# Gates.net
KiCad netlist of a schematic drawn in Altium Designer
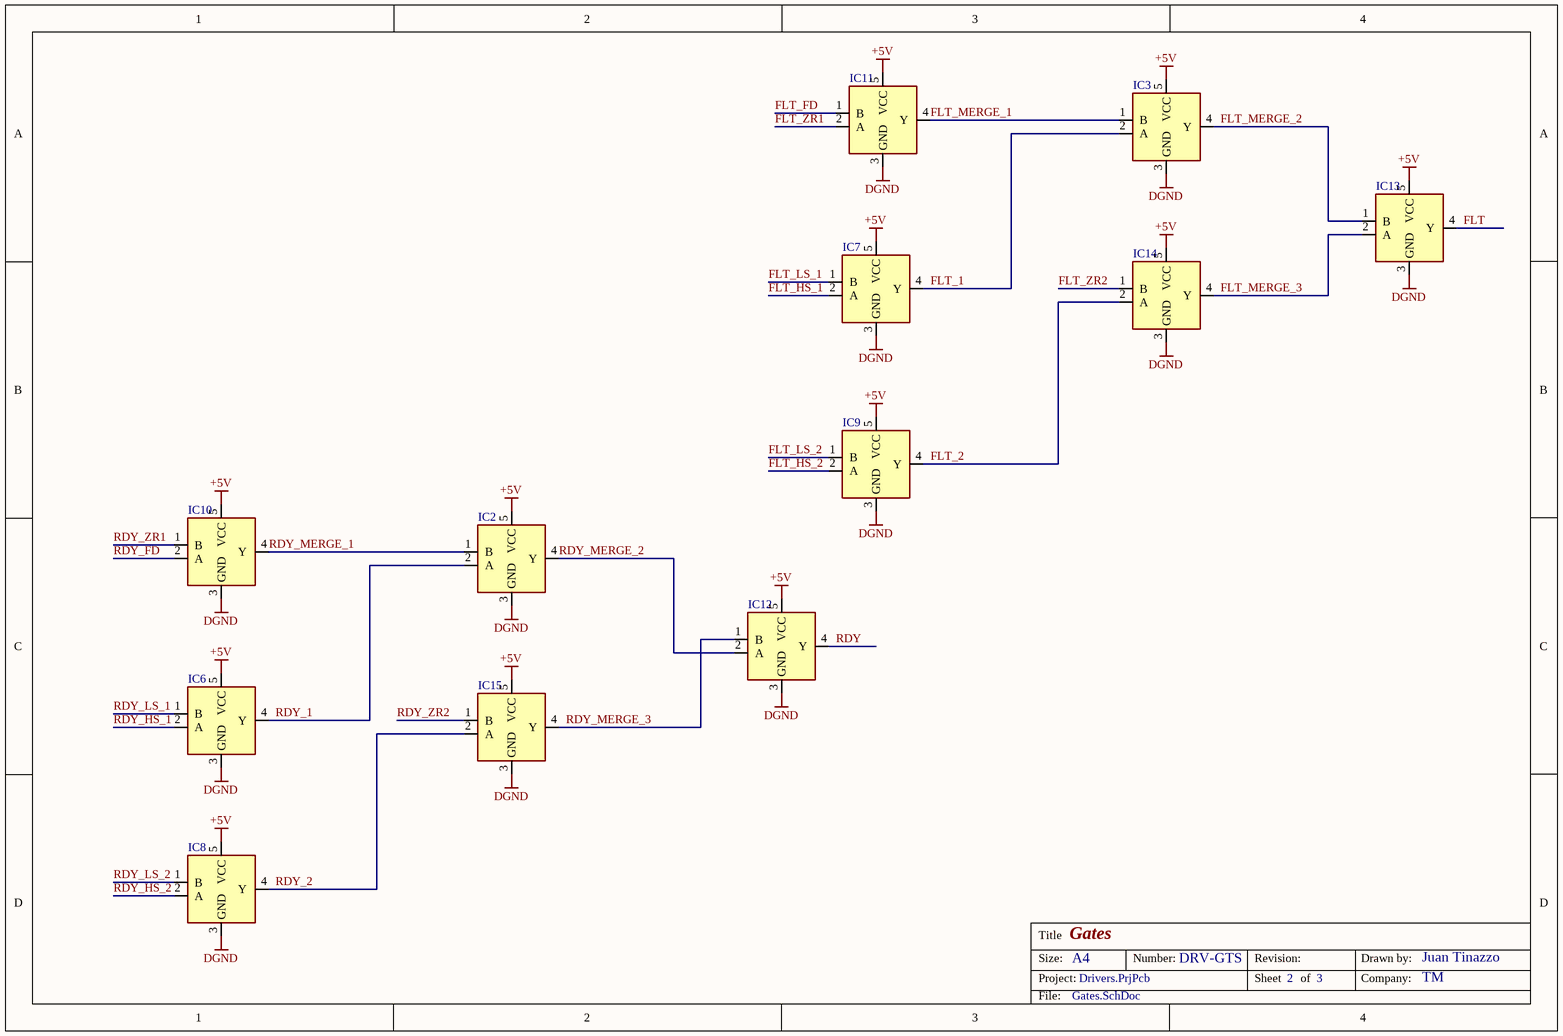
[diagram p0: Gates.SchDoc]

(export (version "E")
  (design (tool "Eeschema 10.0.6"))
  (components
    (comp (ref "IC2")
      (value "74LVC1G08GW,125")
      (footprint "SamacSys:SOT65P210X110-5N")
      (description "Integrated Circuit")
      (fields (field (name "MOUSER PART NUMBER") "771-74LVC1G08GW-G"))
      (libsource (lib "SamacSys") (part "74LVC1G08GW,125"))
    )
    (comp (ref "IC3")
      (value "74LVC1G08GW,125")
      (footprint "SamacSys:SOT65P210X110-5N")
      (description "Integrated Circuit")
      (fields (field (name "MOUSER PART NUMBER") "771-74LVC1G08GW-G"))
      (libsource (lib "SamacSys") (part "74LVC1G08GW,125"))
    )
    (comp (ref "IC6")
      (value "74LVC1G08GW,125")
      (footprint "SamacSys:SOT65P210X110-5N")
      (description "Integrated Circuit")
      (fields (field (name "MOUSER PART NUMBER") "771-74LVC1G08GW-G"))
      (libsource (lib "SamacSys") (part "74LVC1G08GW,125"))
    )
    (comp (ref "IC7")
      (value "74LVC1G08GW,125")
      (footprint "SamacSys:SOT65P210X110-5N")
      (description "Integrated Circuit")
      (fields (field (name "MOUSER PART NUMBER") "771-74LVC1G08GW-G"))
      (libsource (lib "SamacSys") (part "74LVC1G08GW,125"))
    )
    (comp (ref "IC8")
      (value "74LVC1G08GW,125")
      (footprint "SamacSys:SOT65P210X110-5N")
      (description "Integrated Circuit")
      (fields (field (name "MOUSER PART NUMBER") "771-74LVC1G08GW-G"))
      (libsource (lib "SamacSys") (part "74LVC1G08GW,125"))
    )
    (comp (ref "IC9")
      (value "74LVC1G08GW,125")
      (footprint "SamacSys:SOT65P210X110-5N")
      (description "Integrated Circuit")
      (fields (field (name "MOUSER PART NUMBER") "771-74LVC1G08GW-G"))
      (libsource (lib "SamacSys") (part "74LVC1G08GW,125"))
    )
    (comp (ref "IC10")
      (value "74LVC1G08GW,125")
      (footprint "SamacSys:SOT65P210X110-5N")
      (description "Integrated Circuit")
      (fields (field (name "MOUSER PART NUMBER") "771-74LVC1G08GW-G"))
      (libsource (lib "SamacSys") (part "74LVC1G08GW,125"))
    )
    (comp (ref "IC11")
      (value "74LVC1G08GW,125")
      (footprint "SamacSys:SOT65P210X110-5N")
      (description "Integrated Circuit")
      (fields (field (name "MOUSER PART NUMBER") "771-74LVC1G08GW-G"))
      (libsource (lib "SamacSys") (part "74LVC1G08GW,125"))
    )
    (comp (ref "IC12")
      (value "74LVC1G08GW,125")
      (footprint "SamacSys:SOT65P210X110-5N")
      (description "Integrated Circuit")
      (fields (field (name "MOUSER PART NUMBER") "771-74LVC1G08GW-G"))
      (libsource (lib "SamacSys") (part "74LVC1G08GW,125"))
    )
    (comp (ref "IC13")
      (value "74LVC1G08GW,125")
      (footprint "SamacSys:SOT65P210X110-5N")
      (description "Integrated Circuit")
      (fields (field (name "MOUSER PART NUMBER") "771-74LVC1G08GW-G"))
      (libsource (lib "SamacSys") (part "74LVC1G08GW,125"))
    )
    (comp (ref "IC14")
      (value "74LVC1G08GW,125")
      (footprint "SamacSys:SOT65P210X110-5N")
      (description "Integrated Circuit")
      (fields (field (name "MOUSER PART NUMBER") "771-74LVC1G08GW-G"))
      (libsource (lib "SamacSys") (part "74LVC1G08GW,125"))
    )
    (comp (ref "IC15")
      (value "74LVC1G08GW,125")
      (footprint "SamacSys:SOT65P210X110-5N")
      (description "Integrated Circuit")
      (fields (field (name "MOUSER PART NUMBER") "771-74LVC1G08GW-G"))
      (libsource (lib "SamacSys") (part "74LVC1G08GW,125"))
    )
  )
  (nets
    (net (code "1") (name "+5V") (class "Default")
      (node (ref "IC10") (pin "5") (pinfunction "VCC_5") (pintype "passive"))
      (node (ref "IC11") (pin "5") (pinfunction "VCC_5") (pintype "passive"))
      (node (ref "IC12") (pin "5") (pinfunction "VCC_5") (pintype "passive"))
      (node (ref "IC13") (pin "5") (pinfunction "VCC_5") (pintype "passive"))
      (node (ref "IC14") (pin "5") (pinfunction "VCC_5") (pintype "passive"))
      (node (ref "IC15") (pin "5") (pinfunction "VCC_5") (pintype "passive"))
      (node (ref "IC2") (pin "5") (pinfunction "VCC_5") (pintype "passive"))
      (node (ref "IC3") (pin "5") (pinfunction "VCC_5") (pintype "passive"))
      (node (ref "IC6") (pin "5") (pinfunction "VCC_5") (pintype "passive"))
      (node (ref "IC7") (pin "5") (pinfunction "VCC_5") (pintype "passive"))
      (node (ref "IC8") (pin "5") (pinfunction "VCC_5") (pintype "passive"))
      (node (ref "IC9") (pin "5") (pinfunction "VCC_5") (pintype "passive"))
    )
    (net (code "2") (name "/FLT") (class "Default")
      (node (ref "IC13") (pin "4") (pinfunction "Y_4") (pintype "passive"))
    )
    (net (code "3") (name "/FLT_1") (class "Default")
      (node (ref "IC3") (pin "2") (pinfunction "A_2") (pintype "passive"))
      (node (ref "IC7") (pin "4") (pinfunction "Y_4") (pintype "passive"))
    )
    (net (code "4") (name "/FLT_2") (class "Default")
      (node (ref "IC14") (pin "2") (pinfunction "A_2") (pintype "passive"))
      (node (ref "IC9") (pin "4") (pinfunction "Y_4") (pintype "passive"))
    )
    (net (code "5") (name "/FLT_FD") (class "Default")
      (node (ref "IC11") (pin "1") (pinfunction "B_1") (pintype "passive"))
    )
    (net (code "6") (name "/FLT_HS_1") (class "Default")
      (node (ref "IC7") (pin "2") (pinfunction "A_2") (pintype "passive"))
    )
    (net (code "7") (name "/FLT_HS_2") (class "Default")
      (node (ref "IC9") (pin "2") (pinfunction "A_2") (pintype "passive"))
    )
    (net (code "8") (name "/FLT_LS_1") (class "Default")
      (node (ref "IC7") (pin "1") (pinfunction "B_1") (pintype "passive"))
    )
    (net (code "9") (name "/FLT_LS_2") (class "Default")
      (node (ref "IC9") (pin "1") (pinfunction "B_1") (pintype "passive"))
    )
    (net (code "10") (name "/FLT_MERGE_1") (class "Default")
      (node (ref "IC11") (pin "4") (pinfunction "Y_4") (pintype "passive"))
      (node (ref "IC3") (pin "1") (pinfunction "B_1") (pintype "passive"))
    )
    (net (code "11") (name "/FLT_MERGE_2") (class "Default")
      (node (ref "IC13") (pin "1") (pinfunction "B_1") (pintype "passive"))
      (node (ref "IC3") (pin "4") (pinfunction "Y_4") (pintype "passive"))
    )
    (net (code "12") (name "/FLT_MERGE_3") (class "Default")
      (node (ref "IC13") (pin "2") (pinfunction "A_2") (pintype "passive"))
      (node (ref "IC14") (pin "4") (pinfunction "Y_4") (pintype "passive"))
    )
    (net (code "13") (name "/FLT_ZR1") (class "Default")
      (node (ref "IC11") (pin "2") (pinfunction "A_2") (pintype "passive"))
    )
    (net (code "14") (name "/FLT_ZR2") (class "Default")
      (node (ref "IC14") (pin "1") (pinfunction "B_1") (pintype "passive"))
    )
    (net (code "15") (name "/RDY") (class "Default")
      (node (ref "IC12") (pin "4") (pinfunction "Y_4") (pintype "passive"))
    )
    (net (code "16") (name "/RDY_1") (class "Default")
      (node (ref "IC2") (pin "2") (pinfunction "A_2") (pintype "passive"))
      (node (ref "IC6") (pin "4") (pinfunction "Y_4") (pintype "passive"))
    )
    (net (code "17") (name "/RDY_2") (class "Default")
      (node (ref "IC15") (pin "2") (pinfunction "A_2") (pintype "passive"))
      (node (ref "IC8") (pin "4") (pinfunction "Y_4") (pintype "passive"))
    )
    (net (code "18") (name "/RDY_FD") (class "Default")
      (node (ref "IC10") (pin "2") (pinfunction "A_2") (pintype "passive"))
    )
    (net (code "19") (name "/RDY_HS_1") (class "Default")
      (node (ref "IC6") (pin "2") (pinfunction "A_2") (pintype "passive"))
    )
    (net (code "20") (name "/RDY_HS_2") (class "Default")
      (node (ref "IC8") (pin "2") (pinfunction "A_2") (pintype "passive"))
    )
    (net (code "21") (name "/RDY_LS_1") (class "Default")
      (node (ref "IC6") (pin "1") (pinfunction "B_1") (pintype "passive"))
    )
    (net (code "22") (name "/RDY_LS_2") (class "Default")
      (node (ref "IC8") (pin "1") (pinfunction "B_1") (pintype "passive"))
    )
    (net (code "23") (name "/RDY_MERGE_1") (class "Default")
      (node (ref "IC10") (pin "4") (pinfunction "Y_4") (pintype "passive"))
      (node (ref "IC2") (pin "1") (pinfunction "B_1") (pintype "passive"))
    )
    (net (code "24") (name "/RDY_MERGE_2") (class "Default")
      (node (ref "IC12") (pin "2") (pinfunction "A_2") (pintype "passive"))
      (node (ref "IC2") (pin "4") (pinfunction "Y_4") (pintype "passive"))
    )
    (net (code "25") (name "/RDY_MERGE_3") (class "Default")
      (node (ref "IC12") (pin "1") (pinfunction "B_1") (pintype "passive"))
      (node (ref "IC15") (pin "4") (pinfunction "Y_4") (pintype "passive"))
    )
    (net (code "26") (name "/RDY_ZR1") (class "Default")
      (node (ref "IC10") (pin "1") (pinfunction "B_1") (pintype "passive"))
    )
    (net (code "27") (name "/RDY_ZR2") (class "Default")
      (node (ref "IC15") (pin "1") (pinfunction "B_1") (pintype "passive"))
    )
    (net (code "28") (name "DGND") (class "Default")
      (node (ref "IC10") (pin "3") (pinfunction "GND_3") (pintype "passive"))
      (node (ref "IC11") (pin "3") (pinfunction "GND_3") (pintype "passive"))
      (node (ref "IC12") (pin "3") (pinfunction "GND_3") (pintype "passive"))
      (node (ref "IC13") (pin "3") (pinfunction "GND_3") (pintype "passive"))
      (node (ref "IC14") (pin "3") (pinfunction "GND_3") (pintype "passive"))
      (node (ref "IC15") (pin "3") (pinfunction "GND_3") (pintype "passive"))
      (node (ref "IC2") (pin "3") (pinfunction "GND_3") (pintype "passive"))
      (node (ref "IC3") (pin "3") (pinfunction "GND_3") (pintype "passive"))
      (node (ref "IC6") (pin "3") (pinfunction "GND_3") (pintype "passive"))
      (node (ref "IC7") (pin "3") (pinfunction "GND_3") (pintype "passive"))
      (node (ref "IC8") (pin "3") (pinfunction "GND_3") (pintype "passive"))
      (node (ref "IC9") (pin "3") (pinfunction "GND_3") (pintype "passive"))
    )
  )
)
